# LEDs.net
KiCad netlist of a schematic drawn in Altium Designer
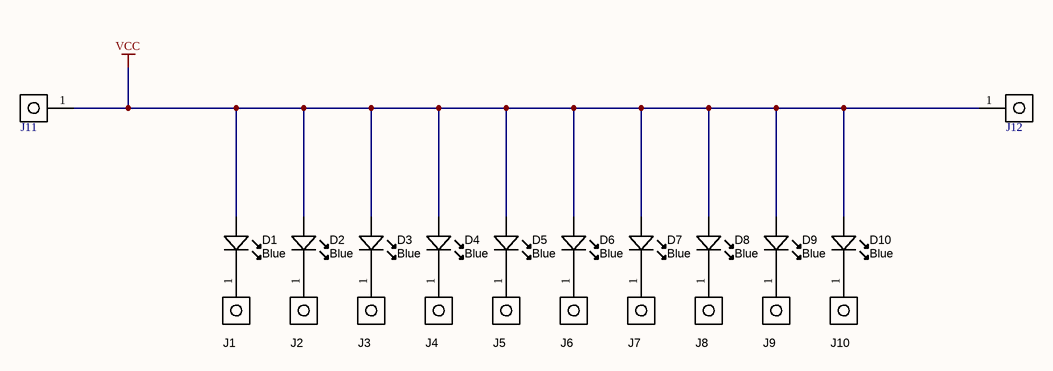
[diagram p0: LEDs.SchDoc]

(export (version "E")
  (design (tool "Eeschema 10.0.6"))
  (components
    (comp (ref "D1")
      (value "Blue")
      (footprint "LED-0805S-SIDELED-2.1X0.6X1.0")
      (description "LED 0805 SIDELED SMD Green 250mcd 525nm")
      (fields (field (name "COLOR") "Blue"))
      (libsource (lib "PBL - Light Sources") (part "LED_SMD_PureGreen_0805RA_250mcd"))
    )
    (comp (ref "D2")
      (value "Blue")
      (footprint "LED-0805S-SIDELED-2.1X0.6X1.0")
      (description "LED 0805 SIDELED SMD Green 250mcd 525nm")
      (fields (field (name "COLOR") "Blue"))
      (libsource (lib "PBL - Light Sources") (part "LED_SMD_PureGreen_0805RA_250mcd"))
    )
    (comp (ref "D3")
      (value "Blue")
      (footprint "LED-0805S-SIDELED-2.1X0.6X1.0")
      (description "LED 0805 SIDELED SMD Green 250mcd 525nm")
      (fields (field (name "COLOR") "Blue"))
      (libsource (lib "PBL - Light Sources") (part "LED_SMD_PureGreen_0805RA_250mcd"))
    )
    (comp (ref "D4")
      (value "Blue")
      (footprint "LED-0805S-SIDELED-2.1X0.6X1.0")
      (description "LED 0805 SIDELED SMD Green 250mcd 525nm")
      (fields (field (name "COLOR") "Blue"))
      (libsource (lib "PBL - Light Sources") (part "LED_SMD_PureGreen_0805RA_250mcd"))
    )
    (comp (ref "D5")
      (value "Blue")
      (footprint "LED-0805S-SIDELED-2.1X0.6X1.0")
      (description "LED 0805 SIDELED SMD Green 250mcd 525nm")
      (fields (field (name "COLOR") "Blue"))
      (libsource (lib "PBL - Light Sources") (part "LED_SMD_PureGreen_0805RA_250mcd"))
    )
    (comp (ref "D6")
      (value "Blue")
      (footprint "LED-0805S-SIDELED-2.1X0.6X1.0")
      (description "LED 0805 SIDELED SMD Green 250mcd 525nm")
      (fields (field (name "COLOR") "Blue"))
      (libsource (lib "PBL - Light Sources") (part "LED_SMD_PureGreen_0805RA_250mcd"))
    )
    (comp (ref "D7")
      (value "Blue")
      (footprint "LED-0805S-SIDELED-2.1X0.6X1.0")
      (description "LED 0805 SIDELED SMD Green 250mcd 525nm")
      (fields (field (name "COLOR") "Blue"))
      (libsource (lib "PBL - Light Sources") (part "LED_SMD_PureGreen_0805RA_250mcd"))
    )
    (comp (ref "D8")
      (value "Blue")
      (footprint "LED-0805S-SIDELED-2.1X0.6X1.0")
      (description "LED 0805 SIDELED SMD Green 250mcd 525nm")
      (fields (field (name "COLOR") "Blue"))
      (libsource (lib "PBL - Light Sources") (part "LED_SMD_PureGreen_0805RA_250mcd"))
    )
    (comp (ref "D9")
      (value "Blue")
      (footprint "LED-0805S-SIDELED-2.1X0.6X1.0")
      (description "LED 0805 SIDELED SMD Green 250mcd 525nm")
      (fields (field (name "COLOR") "Blue"))
      (libsource (lib "PBL - Light Sources") (part "LED_SMD_PureGreen_0805RA_250mcd"))
    )
    (comp (ref "D10")
      (value "Blue")
      (footprint "LED-0805S-SIDELED-2.1X0.6X1.0")
      (description "LED 0805 SIDELED SMD Green 250mcd 525nm")
      (fields (field (name "COLOR") "Blue"))
      (libsource (lib "PBL - Light Sources") (part "LED_SMD_PureGreen_0805RA_250mcd"))
    )
    (comp (ref "J1")
      (value "CONN_SOCKET_1x1P_0.100in")
      (footprint "1x1POS_SOCKET_LOWPROF")
      (description "Socket header THT 1-Pos Low profile Single-row 2.54mm pitch")
      (libsource (lib "PBL - Connectors") (part "CONN_SOCKET_1x1P_0.100in"))
    )
    (comp (ref "J2")
      (value "CONN_SOCKET_1x1P_0.100in")
      (footprint "1x1POS_SOCKET_LOWPROF")
      (description "Socket header THT 1-Pos Low profile Single-row 2.54mm pitch")
      (libsource (lib "PBL - Connectors") (part "CONN_SOCKET_1x1P_0.100in"))
    )
    (comp (ref "J3")
      (value "CONN_SOCKET_1x1P_0.100in")
      (footprint "1x1POS_SOCKET_LOWPROF")
      (description "Socket header THT 1-Pos Low profile Single-row 2.54mm pitch")
      (libsource (lib "PBL - Connectors") (part "CONN_SOCKET_1x1P_0.100in"))
    )
    (comp (ref "J4")
      (value "CONN_SOCKET_1x1P_0.100in")
      (footprint "1x1POS_SOCKET_LOWPROF")
      (description "Socket header THT 1-Pos Low profile Single-row 2.54mm pitch")
      (libsource (lib "PBL - Connectors") (part "CONN_SOCKET_1x1P_0.100in"))
    )
    (comp (ref "J5")
      (value "CONN_SOCKET_1x1P_0.100in")
      (footprint "1x1POS_SOCKET_LOWPROF")
      (description "Socket header THT 1-Pos Low profile Single-row 2.54mm pitch")
      (libsource (lib "PBL - Connectors") (part "CONN_SOCKET_1x1P_0.100in"))
    )
    (comp (ref "J6")
      (value "CONN_SOCKET_1x1P_0.100in")
      (footprint "1x1POS_SOCKET_LOWPROF")
      (description "Socket header THT 1-Pos Low profile Single-row 2.54mm pitch")
      (libsource (lib "PBL - Connectors") (part "CONN_SOCKET_1x1P_0.100in"))
    )
    (comp (ref "J7")
      (value "CONN_SOCKET_1x1P_0.100in")
      (footprint "1x1POS_SOCKET_LOWPROF")
      (description "Socket header THT 1-Pos Low profile Single-row 2.54mm pitch")
      (libsource (lib "PBL - Connectors") (part "CONN_SOCKET_1x1P_0.100in"))
    )
    (comp (ref "J8")
      (value "CONN_SOCKET_1x1P_0.100in")
      (footprint "1x1POS_SOCKET_LOWPROF")
      (description "Socket header THT 1-Pos Low profile Single-row 2.54mm pitch")
      (libsource (lib "PBL - Connectors") (part "CONN_SOCKET_1x1P_0.100in"))
    )
    (comp (ref "J9")
      (value "CONN_SOCKET_1x1P_0.100in")
      (footprint "1x1POS_SOCKET_LOWPROF")
      (description "Socket header THT 1-Pos Low profile Single-row 2.54mm pitch")
      (libsource (lib "PBL - Connectors") (part "CONN_SOCKET_1x1P_0.100in"))
    )
    (comp (ref "J10")
      (value "CONN_SOCKET_1x1P_0.100in")
      (footprint "1x1POS_SOCKET_LOWPROF")
      (description "Socket header THT 1-Pos Low profile Single-row 2.54mm pitch")
      (libsource (lib "PBL - Connectors") (part "CONN_SOCKET_1x1P_0.100in"))
    )
    (comp (ref "J11")
      (value "CONN_SOCKET_1x1P_0.100in")
      (footprint "1x1POS_SOCKET_LOWPROF")
      (description "Socket header THT 1-Pos Low profile Single-row 2.54mm pitch")
      (libsource (lib "") (part "CONN_SOCKET_1x1P_0.100in_1"))
    )
    (comp (ref "J12")
      (value "CONN_SOCKET_1x1P_0.100in")
      (footprint "1x1POS_SOCKET_LOWPROF")
      (description "Socket header THT 1-Pos Low profile Single-row 2.54mm pitch")
      (libsource (lib "") (part "CONN_SOCKET_1x1P_0.100in_2"))
    )
  )
  (nets
    (net (code "1") (name "Net-(D1-PadK)") (class "Default")
      (node (ref "D1") (pin "K") (pinfunction "K_K") (pintype "passive"))
      (node (ref "J1") (pin "1") (pinfunction "1_1") (pintype "passive"))
    )
    (net (code "2") (name "Net-(D2-PadK)") (class "Default")
      (node (ref "D2") (pin "K") (pinfunction "K_K") (pintype "passive"))
      (node (ref "J2") (pin "1") (pinfunction "1_1") (pintype "passive"))
    )
    (net (code "3") (name "Net-(D3-PadK)") (class "Default")
      (node (ref "D3") (pin "K") (pinfunction "K_K") (pintype "passive"))
      (node (ref "J3") (pin "1") (pinfunction "1_1") (pintype "passive"))
    )
    (net (code "4") (name "Net-(D4-PadK)") (class "Default")
      (node (ref "D4") (pin "K") (pinfunction "K_K") (pintype "passive"))
      (node (ref "J4") (pin "1") (pinfunction "1_1") (pintype "passive"))
    )
    (net (code "5") (name "Net-(D5-PadK)") (class "Default")
      (node (ref "D5") (pin "K") (pinfunction "K_K") (pintype "passive"))
      (node (ref "J5") (pin "1") (pinfunction "1_1") (pintype "passive"))
    )
    (net (code "6") (name "Net-(D6-PadK)") (class "Default")
      (node (ref "D6") (pin "K") (pinfunction "K_K") (pintype "passive"))
      (node (ref "J6") (pin "1") (pinfunction "1_1") (pintype "passive"))
    )
    (net (code "7") (name "Net-(D7-PadK)") (class "Default")
      (node (ref "D7") (pin "K") (pinfunction "K_K") (pintype "passive"))
      (node (ref "J7") (pin "1") (pinfunction "1_1") (pintype "passive"))
    )
    (net (code "8") (name "Net-(D8-PadK)") (class "Default")
      (node (ref "D8") (pin "K") (pinfunction "K_K") (pintype "passive"))
      (node (ref "J8") (pin "1") (pinfunction "1_1") (pintype "passive"))
    )
    (net (code "9") (name "Net-(D9-PadK)") (class "Default")
      (node (ref "D9") (pin "K") (pinfunction "K_K") (pintype "passive"))
      (node (ref "J9") (pin "1") (pinfunction "1_1") (pintype "passive"))
    )
    (net (code "10") (name "Net-(D10-PadK)") (class "Default")
      (node (ref "D10") (pin "K") (pinfunction "K_K") (pintype "passive"))
      (node (ref "J10") (pin "1") (pinfunction "1_1") (pintype "passive"))
    )
    (net (code "11") (name "VCC") (class "Default")
      (node (ref "D1") (pin "A") (pinfunction "A_A") (pintype "passive"))
      (node (ref "D10") (pin "A") (pinfunction "A_A") (pintype "passive"))
      (node (ref "D2") (pin "A") (pinfunction "A_A") (pintype "passive"))
      (node (ref "D3") (pin "A") (pinfunction "A_A") (pintype "passive"))
      (node (ref "D4") (pin "A") (pinfunction "A_A") (pintype "passive"))
      (node (ref "D5") (pin "A") (pinfunction "A_A") (pintype "passive"))
      (node (ref "D6") (pin "A") (pinfunction "A_A") (pintype "passive"))
      (node (ref "D7") (pin "A") (pinfunction "A_A") (pintype "passive"))
      (node (ref "D8") (pin "A") (pinfunction "A_A") (pintype "passive"))
      (node (ref "D9") (pin "A") (pinfunction "A_A") (pintype "passive"))
      (node (ref "J11") (pin "1") (pinfunction "1_1") (pintype "passive"))
      (node (ref "J12") (pin "1") (pinfunction "1_1") (pintype "passive"))
    )
  )
)
